# fpga_power.net
KiCad netlist of a schematic drawn in Altium Designer
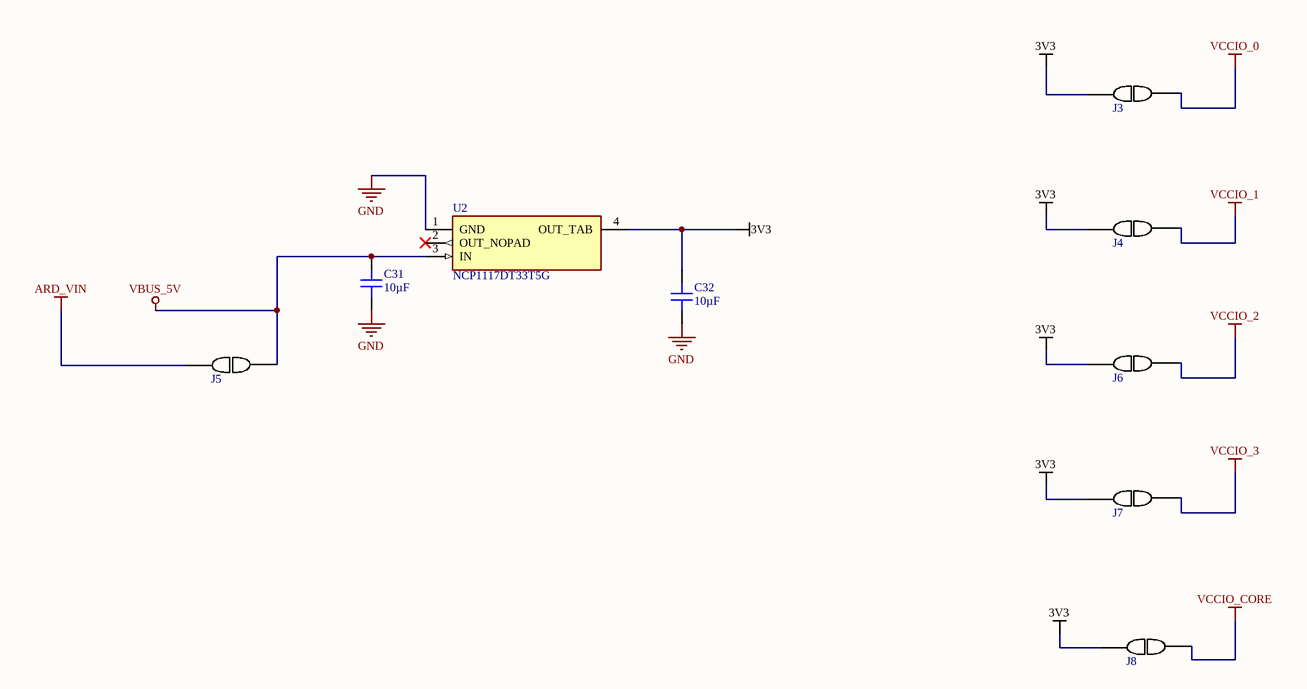
[diagram p0: fpga_power.SchDoc]

(export (version "E")
  (design (tool "Eeschema 10.0.6"))
  (components
    (comp (ref "C31")
      (value "10µF")
      (footprint "CAP 0603_1608")
      (description "CAP CER 10UF 16V X5R 0603")
      (fields
        (field (name "PART NUMBER") "GRT188R61C106KE13D")
        (field (name "MANUFACTURER") "Murata Electronics")
      )
      (libsource (lib "Celestial Altium Library - altium_library (2)") (part "Capacitor"))
    )
    (comp (ref "C32")
      (value "10µF")
      (footprint "CAP 0603_1608")
      (description "CAP CER 10UF 16V X5R 0603")
      (fields
        (field (name "PART NUMBER") "GRT188R61C106KE13D")
        (field (name "MANUFACTURER") "Murata Electronics")
      )
      (libsource (lib "Celestial Altium Library - altium_library (2)") (part "Capacitor"))
    )
    (comp (ref "J3")
      (value "103185-2")
      (footprint "TE_103185-2")
      (description "02 MODII HDR SRST B/A .100CL")
      (libsource (lib "103185-2") (part "103185-2"))
    )
    (comp (ref "J4")
      (value "103185-2")
      (footprint "TE_103185-2")
      (description "02 MODII HDR SRST B/A .100CL")
      (libsource (lib "103185-2") (part "103185-2"))
    )
    (comp (ref "J5")
      (value "103185-2")
      (footprint "TE_103185-2")
      (description "02 MODII HDR SRST B/A .100CL")
      (libsource (lib "103185-2") (part "103185-2"))
    )
    (comp (ref "J6")
      (value "103185-2")
      (footprint "TE_103185-2")
      (description "02 MODII HDR SRST B/A .100CL")
      (libsource (lib "103185-2") (part "103185-2"))
    )
    (comp (ref "J7")
      (value "103185-2")
      (footprint "TE_103185-2")
      (description "02 MODII HDR SRST B/A .100CL")
      (libsource (lib "103185-2") (part "103185-2"))
    )
    (comp (ref "J8")
      (value "103185-2")
      (footprint "TE_103185-2")
      (description "02 MODII HDR SRST B/A .100CL")
      (libsource (lib "103185-2") (part "103185-2"))
    )
    (comp (ref "U2")
      (value "NCP1117DT33T5G")
      (footprint "SamacSys:TO229P990X238-4N")
      (description "Integrated Circuit")
      (fields (field (name "MOUSER PART NUMBER") "863-NCP1117DT33T5G"))
      (libsource (lib "SamacSys") (part "NCP1117DT33T5G"))
    )
  )
  (nets
    (net (code "1") (name "3V3") (class "Default")
      (node (ref "C32") (pin "1") (pinfunction "1_1") (pintype "passive"))
      (node (ref "J3") (pin "1") (pinfunction "1_1") (pintype "passive"))
      (node (ref "J4") (pin "1") (pinfunction "1_1") (pintype "passive"))
      (node (ref "J6") (pin "1") (pinfunction "1_1") (pintype "passive"))
      (node (ref "J7") (pin "1") (pinfunction "1_1") (pintype "passive"))
      (node (ref "J8") (pin "1") (pinfunction "1_1") (pintype "passive"))
      (node (ref "U2") (pin "4") (pinfunction "OUT_TAB_4") (pintype "power_in"))
    )
    (net (code "2") (name "ARD_VIN") (class "Default")
      (node (ref "J5") (pin "2") (pinfunction "2_2") (pintype "passive"))
    )
    (net (code "3") (name "GND") (class "Default")
      (node (ref "C31") (pin "1") (pinfunction "1_1") (pintype "passive"))
      (node (ref "C32") (pin "2") (pinfunction "2_2") (pintype "passive"))
      (node (ref "U2") (pin "1") (pinfunction "GND_1") (pintype "power_in"))
    )
    (net (code "4") (name "VBUS_5V") (class "Default")
      (node (ref "C31") (pin "2") (pinfunction "2_2") (pintype "passive"))
      (node (ref "J5") (pin "1") (pinfunction "1_1") (pintype "passive"))
      (node (ref "U2") (pin "3") (pinfunction "IN_3") (pintype "input"))
    )
    (net (code "5") (name "VCCIO_0") (class "Default")
      (node (ref "J3") (pin "2") (pinfunction "2_2") (pintype "passive"))
    )
    (net (code "6") (name "VCCIO_1") (class "Default")
      (node (ref "J4") (pin "2") (pinfunction "2_2") (pintype "passive"))
    )
    (net (code "7") (name "VCCIO_2") (class "Default")
      (node (ref "J6") (pin "2") (pinfunction "2_2") (pintype "passive"))
    )
    (net (code "8") (name "VCCIO_3") (class "Default")
      (node (ref "J7") (pin "2") (pinfunction "2_2") (pintype "passive"))
    )
    (net (code "9") (name "VCCIO_CORE") (class "Default")
      (node (ref "J8") (pin "2") (pinfunction "2_2") (pintype "passive"))
    )
    (net (code "10") (name "unconnected-(U2-OUT_NOPAD-Pad2)") (class "Default")
      (node (ref "U2") (pin "2") (pinfunction "OUT_NOPAD_2") (pintype "output+no_connect"))
    )
  )
)
